# M127A.net
KiCad netlist of a schematic drawn in EAGLE
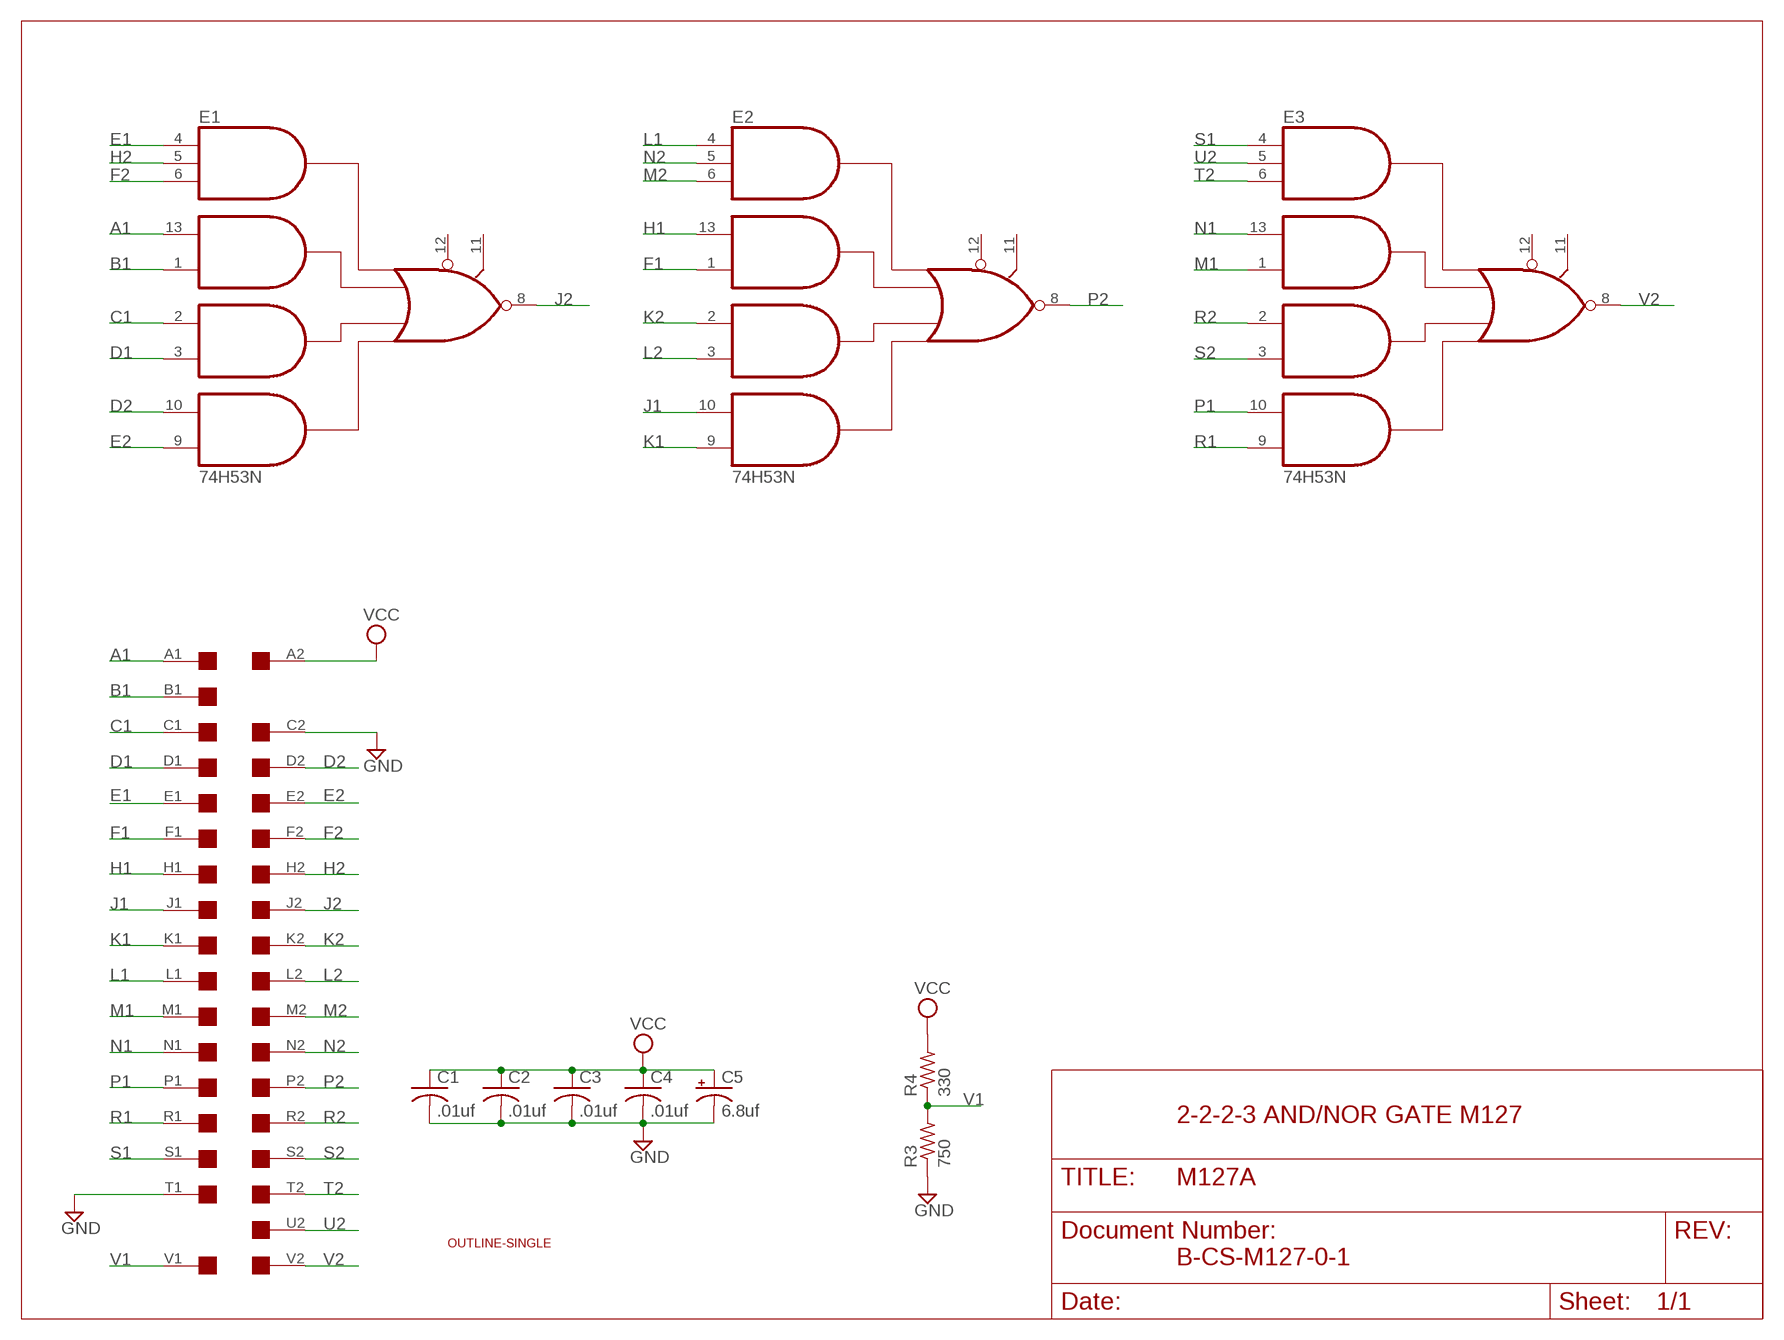
[diagram p0: schematic, sheet 1]

(export (version "E")
  (design (tool "Eeschema 10.0.6"))
  (components
    (comp (ref "C1")
      (value ".01uf")
      (footprint "eagle-import:C050-025X075")
      (libsource (lib "eagle-import") (part "C-US050-025X075"))
    )
    (comp (ref "C2")
      (value ".01uf")
      (footprint "eagle-import:C050-025X075")
      (libsource (lib "eagle-import") (part "C-US050-025X075"))
    )
    (comp (ref "C3")
      (value ".01uf")
      (footprint "eagle-import:C050-025X075")
      (libsource (lib "eagle-import") (part "C-US050-025X075"))
    )
    (comp (ref "C4")
      (value ".01uf")
      (footprint "eagle-import:C050-025X075")
      (libsource (lib "eagle-import") (part "C-US050-025X075"))
    )
    (comp (ref "C5")
      (value "6.8uf")
      (footprint "eagle-import:E15-5")
      (libsource (lib "eagle-import") (part "CPOL-USE15-5AXIAL"))
    )
    (comp (ref "E1")
      (value "74H53N")
      (footprint "eagle-import:DIL14")
      (libsource (lib "eagle-import") (part "74H53N"))
    )
    (comp (ref "E2")
      (value "74H53N")
      (footprint "eagle-import:DIL14")
      (libsource (lib "eagle-import") (part "74H53N"))
    )
    (comp (ref "E3")
      (value "74H53N")
      (footprint "eagle-import:DIL14")
      (libsource (lib "eagle-import") (part "74H53N"))
    )
    (comp (ref "R3")
      (value "750")
      (footprint "eagle-import:0207_10")
      (libsource (lib "eagle-import") (part "R-US_0207/10"))
    )
    (comp (ref "R4")
      (value "330")
      (footprint "eagle-import:0207_10")
      (libsource (lib "eagle-import") (part "R-US_0207/10"))
    )
    (comp (ref "U$1")
      (value "OUTLINE-SINGLE")
      (footprint "eagle-import:SINGLE")
      (libsource (lib "eagle-import") (part "OUTLINE-SINGLE"))
    )
    (comp (ref "U$4")
      (value "SINGLE")
      (footprint "eagle-import:EDGE-CON2")
      (libsource (lib "eagle-import") (part "SINGLE"))
    )
  )
  (nets
    (net (code "1") (name "/A1") (class "Default")
      (node (ref "E1") (pin "13") (pinfunction "I3_13") (pintype "input"))
      (node (ref "U$4") (pin "A1") (pinfunction "1_A1") (pintype "bidirectional"))
    )
    (net (code "2") (name "/B1") (class "Default")
      (node (ref "E1") (pin "1") (pinfunction "I4_1") (pintype "input"))
      (node (ref "U$4") (pin "B1") (pinfunction "1_B1") (pintype "bidirectional"))
    )
    (net (code "3") (name "/C1") (class "Default")
      (node (ref "E1") (pin "2") (pinfunction "I5_2") (pintype "input"))
      (node (ref "U$4") (pin "C1") (pinfunction "1_C1") (pintype "bidirectional"))
    )
    (net (code "4") (name "/D1") (class "Default")
      (node (ref "E1") (pin "3") (pinfunction "I6_3") (pintype "input"))
      (node (ref "U$4") (pin "D1") (pinfunction "1_D1") (pintype "bidirectional"))
    )
    (net (code "5") (name "/D2") (class "Default")
      (node (ref "E1") (pin "10") (pinfunction "I7_10") (pintype "input"))
      (node (ref "U$4") (pin "D2") (pinfunction "1_D2") (pintype "bidirectional"))
    )
    (net (code "6") (name "/E1") (class "Default")
      (node (ref "E1") (pin "4") (pinfunction "I1_4") (pintype "input"))
      (node (ref "U$4") (pin "E1") (pinfunction "1_E1") (pintype "bidirectional"))
    )
    (net (code "7") (name "/E2") (class "Default")
      (node (ref "E1") (pin "9") (pinfunction "I8_9") (pintype "input"))
      (node (ref "U$4") (pin "E2") (pinfunction "1_E2") (pintype "bidirectional"))
    )
    (net (code "8") (name "/F1") (class "Default")
      (node (ref "E2") (pin "1") (pinfunction "I4_1") (pintype "input"))
      (node (ref "U$4") (pin "F1") (pinfunction "1_F1") (pintype "bidirectional"))
    )
    (net (code "9") (name "/F2") (class "Default")
      (node (ref "E1") (pin "6") (pinfunction "I2_6") (pintype "input"))
      (node (ref "U$4") (pin "F2") (pinfunction "1_F2") (pintype "bidirectional"))
    )
    (net (code "10") (name "/H1") (class "Default")
      (node (ref "E2") (pin "13") (pinfunction "I3_13") (pintype "input"))
      (node (ref "U$4") (pin "H1") (pinfunction "1_H1") (pintype "bidirectional"))
    )
    (net (code "11") (name "/H2") (class "Default")
      (node (ref "E1") (pin "5") (pinfunction "I11_5") (pintype "input"))
      (node (ref "U$4") (pin "H2") (pinfunction "1_H2") (pintype "bidirectional"))
    )
    (net (code "12") (name "/J1") (class "Default")
      (node (ref "E2") (pin "10") (pinfunction "I7_10") (pintype "input"))
      (node (ref "U$4") (pin "J1") (pinfunction "1_J1") (pintype "bidirectional"))
    )
    (net (code "13") (name "/J2") (class "Default")
      (node (ref "E1") (pin "8") (pinfunction "O_8") (pintype "output"))
      (node (ref "U$4") (pin "J2") (pinfunction "1_J2") (pintype "bidirectional"))
    )
    (net (code "14") (name "/K1") (class "Default")
      (node (ref "E2") (pin "9") (pinfunction "I8_9") (pintype "input"))
      (node (ref "U$4") (pin "K1") (pinfunction "1_K1") (pintype "bidirectional"))
    )
    (net (code "15") (name "/K2") (class "Default")
      (node (ref "E2") (pin "2") (pinfunction "I5_2") (pintype "input"))
      (node (ref "U$4") (pin "K2") (pinfunction "1_K2") (pintype "bidirectional"))
    )
    (net (code "16") (name "/L1") (class "Default")
      (node (ref "E2") (pin "4") (pinfunction "I1_4") (pintype "input"))
      (node (ref "U$4") (pin "L1") (pinfunction "1_L1") (pintype "bidirectional"))
    )
    (net (code "17") (name "/L2") (class "Default")
      (node (ref "E2") (pin "3") (pinfunction "I6_3") (pintype "input"))
      (node (ref "U$4") (pin "L2") (pinfunction "1_L2") (pintype "bidirectional"))
    )
    (net (code "18") (name "/M1") (class "Default")
      (node (ref "E3") (pin "1") (pinfunction "I4_1") (pintype "input"))
      (node (ref "U$4") (pin "M1") (pinfunction "1_M1") (pintype "bidirectional"))
    )
    (net (code "19") (name "/M2") (class "Default")
      (node (ref "E2") (pin "6") (pinfunction "I2_6") (pintype "input"))
      (node (ref "U$4") (pin "M2") (pinfunction "1_M2") (pintype "bidirectional"))
    )
    (net (code "20") (name "/N1") (class "Default")
      (node (ref "E3") (pin "13") (pinfunction "I3_13") (pintype "input"))
      (node (ref "U$4") (pin "N1") (pinfunction "1_N1") (pintype "bidirectional"))
    )
    (net (code "21") (name "/N2") (class "Default")
      (node (ref "E2") (pin "5") (pinfunction "I11_5") (pintype "input"))
      (node (ref "U$4") (pin "N2") (pinfunction "1_N2") (pintype "bidirectional"))
    )
    (net (code "22") (name "/P1") (class "Default")
      (node (ref "E3") (pin "10") (pinfunction "I7_10") (pintype "input"))
      (node (ref "U$4") (pin "P1") (pinfunction "1_P1") (pintype "bidirectional"))
    )
    (net (code "23") (name "/P2") (class "Default")
      (node (ref "E2") (pin "8") (pinfunction "O_8") (pintype "output"))
      (node (ref "U$4") (pin "P2") (pinfunction "1_P2") (pintype "bidirectional"))
    )
    (net (code "24") (name "/R1") (class "Default")
      (node (ref "E3") (pin "9") (pinfunction "I8_9") (pintype "input"))
      (node (ref "U$4") (pin "R1") (pinfunction "1_R1") (pintype "bidirectional"))
    )
    (net (code "25") (name "/R2") (class "Default")
      (node (ref "E3") (pin "2") (pinfunction "I5_2") (pintype "input"))
      (node (ref "U$4") (pin "R2") (pinfunction "1_R2") (pintype "bidirectional"))
    )
    (net (code "26") (name "/S1") (class "Default")
      (node (ref "E3") (pin "4") (pinfunction "I1_4") (pintype "input"))
      (node (ref "U$4") (pin "S1") (pinfunction "1_S1") (pintype "bidirectional"))
    )
    (net (code "27") (name "/S2") (class "Default")
      (node (ref "E3") (pin "3") (pinfunction "I6_3") (pintype "input"))
      (node (ref "U$4") (pin "S2") (pinfunction "1_S2") (pintype "bidirectional"))
    )
    (net (code "28") (name "/T2") (class "Default")
      (node (ref "E3") (pin "6") (pinfunction "I2_6") (pintype "input"))
      (node (ref "U$4") (pin "T2") (pinfunction "1_T2") (pintype "bidirectional"))
    )
    (net (code "29") (name "/U2") (class "Default")
      (node (ref "E3") (pin "5") (pinfunction "I11_5") (pintype "input"))
      (node (ref "U$4") (pin "U2") (pinfunction "1_U2") (pintype "bidirectional"))
    )
    (net (code "30") (name "/V1") (class "Default")
      (node (ref "R3") (pin "2") (pinfunction "2_2") (pintype "passive"))
      (node (ref "R4") (pin "1") (pinfunction "1_1") (pintype "passive"))
      (node (ref "U$4") (pin "V1") (pinfunction "1_V1") (pintype "bidirectional"))
    )
    (net (code "31") (name "/V2") (class "Default")
      (node (ref "E3") (pin "8") (pinfunction "O_8") (pintype "output"))
      (node (ref "U$4") (pin "V2") (pinfunction "1_V2") (pintype "bidirectional"))
    )
    (net (code "32") (name "GND") (class "Default")
      (node (ref "C1") (pin "2") (pinfunction "2_2") (pintype "passive"))
      (node (ref "C2") (pin "2") (pinfunction "2_2") (pintype "passive"))
      (node (ref "C3") (pin "2") (pinfunction "2_2") (pintype "passive"))
      (node (ref "C4") (pin "2") (pinfunction "2_2") (pintype "passive"))
      (node (ref "C5") (pin "-") (pinfunction "-_-") (pintype "passive"))
      (node (ref "R3") (pin "1") (pinfunction "1_1") (pintype "passive"))
      (node (ref "U$4") (pin "C2") (pinfunction "1_C2") (pintype "bidirectional"))
      (node (ref "U$4") (pin "T1") (pinfunction "1_T1") (pintype "bidirectional"))
    )
    (net (code "33") (name "VCC") (class "Default")
      (node (ref "C1") (pin "1") (pinfunction "1_1") (pintype "passive"))
      (node (ref "C2") (pin "1") (pinfunction "1_1") (pintype "passive"))
      (node (ref "C3") (pin "1") (pinfunction "1_1") (pintype "passive"))
      (node (ref "C4") (pin "1") (pinfunction "1_1") (pintype "passive"))
      (node (ref "C5") (pin "+") (pinfunction "+_+") (pintype "passive"))
      (node (ref "R4") (pin "2") (pinfunction "2_2") (pintype "passive"))
      (node (ref "U$4") (pin "A2") (pinfunction "1_A2") (pintype "bidirectional"))
    )
    (net (code "34") (name "unconnected-(E1A-I9-Pad12)") (class "Default")
      (node (ref "E1") (pin "12") (pinfunction "I9_12") (pintype "passive"))
    )
    (net (code "35") (name "unconnected-(E1A-I10-Pad11)") (class "Default")
      (node (ref "E1") (pin "11") (pinfunction "I10_11") (pintype "passive"))
    )
    (net (code "36") (name "unconnected-(E2A-I9-Pad12)") (class "Default")
      (node (ref "E2") (pin "12") (pinfunction "I9_12") (pintype "passive"))
    )
    (net (code "37") (name "unconnected-(E2A-I10-Pad11)") (class "Default")
      (node (ref "E2") (pin "11") (pinfunction "I10_11") (pintype "passive"))
    )
    (net (code "38") (name "unconnected-(E3A-I9-Pad12)") (class "Default")
      (node (ref "E3") (pin "12") (pinfunction "I9_12") (pintype "passive"))
    )
    (net (code "39") (name "unconnected-(E3A-I10-Pad11)") (class "Default")
      (node (ref "E3") (pin "11") (pinfunction "I10_11") (pintype "passive"))
    )
  )
)
